# hb-featherwing_v2.net
KiCad netlist of a schematic drawn in EAGLE
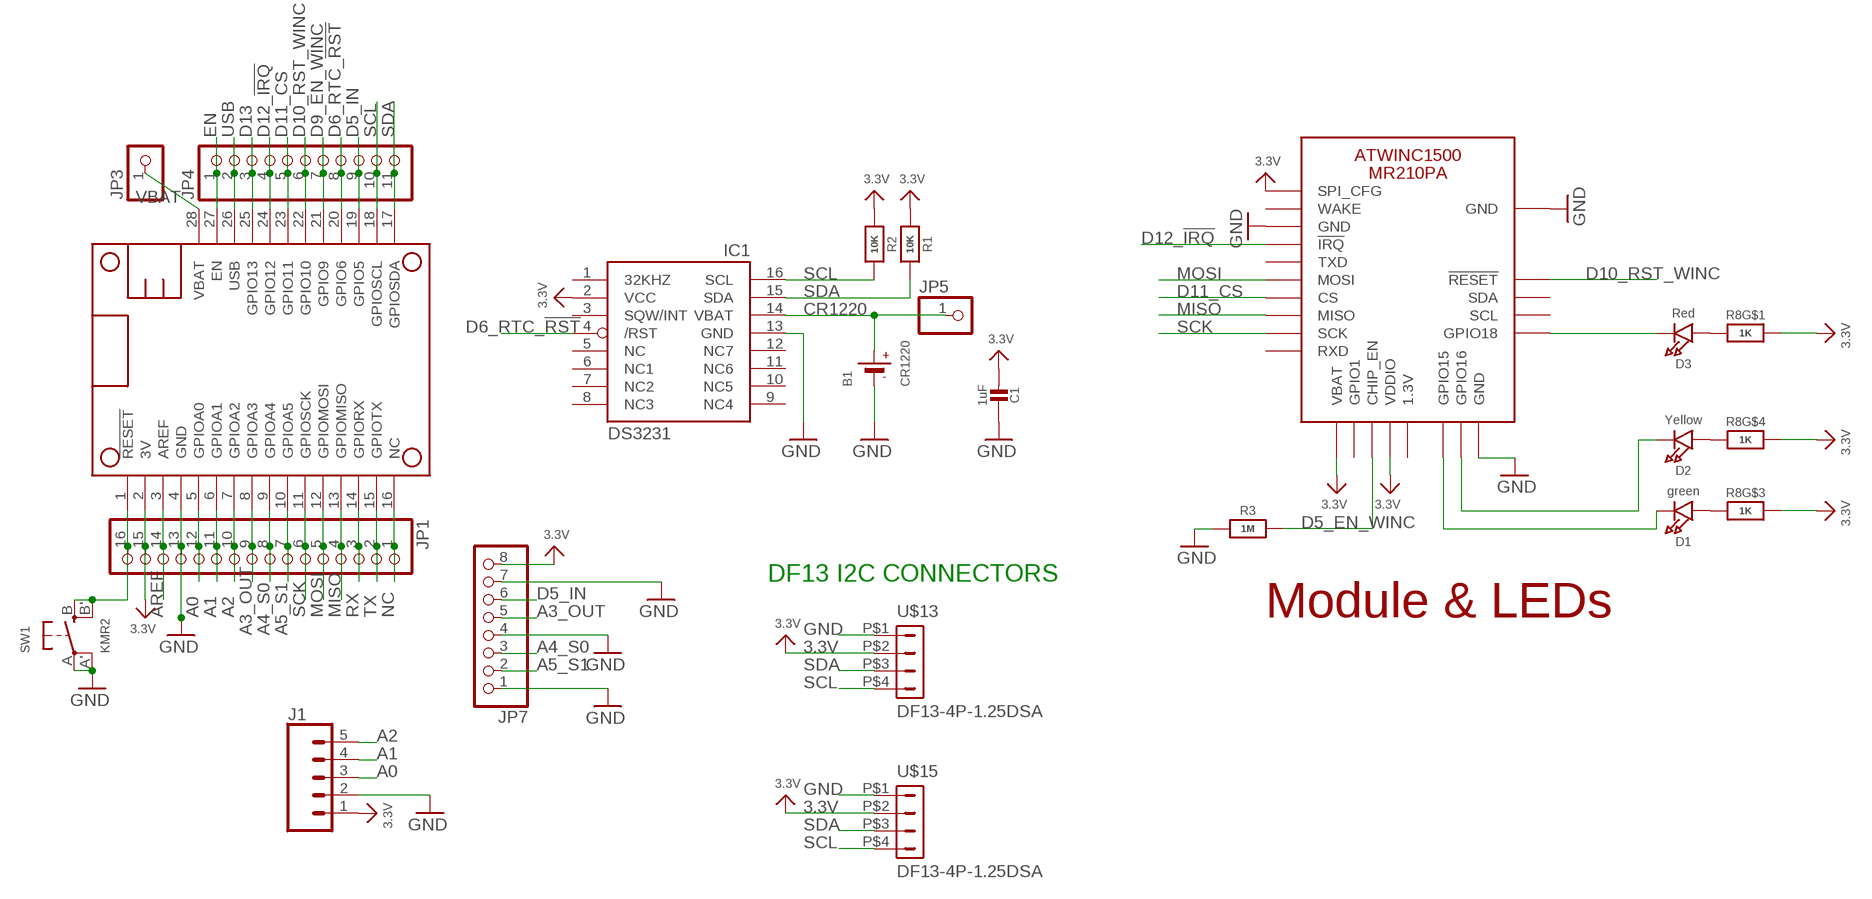
[diagram p0: schematic, sheet 1]

(export (version "E")
  (design (tool "Eeschema 10.0.6"))
  (components
    (comp (ref "B1")
      (value "CR1220")
      (footprint "eagle-import:CR1220-2")
      (libsource (lib "eagle-import") (part "BATTERYCR1220_2"))
    )
    (comp (ref "C1")
      (value "1uF")
      (footprint "eagle-import:0805-NO")
      (libsource (lib "eagle-import") (part "CAP_CERAMIC0805-NOOUTLINE"))
    )
    (comp (ref "D1")
      (value "green")
      (footprint "eagle-import:CHIPLED_0805_NOOUTLINE")
      (libsource (lib "eagle-import") (part "LED0805_NOOUTLINE"))
    )
    (comp (ref "D2")
      (value "Yellow")
      (footprint "eagle-import:CHIPLED_0805_NOOUTLINE")
      (libsource (lib "eagle-import") (part "LED0805_NOOUTLINE"))
    )
    (comp (ref "D3")
      (value "Red")
      (footprint "eagle-import:CHIPLED_0805_NOOUTLINE")
      (libsource (lib "eagle-import") (part "LED0805_NOOUTLINE"))
    )
    (comp (ref "IC1")
      (value "DS3231/SO")
      (footprint "eagle-import:SO16W")
      (libsource (lib "eagle-import") (part "DS3231/SO"))
    )
    (comp (ref "J1")
      (value "CONN_05")
      (footprint "eagle-import:1X05")
      (libsource (lib "eagle-import") (part "CONN_05"))
    )
    (comp (ref "JP1")
      (value "HEADER-1X16ROUND")
      (footprint "eagle-import:1X16_ROUND")
      (libsource (lib "eagle-import") (part "HEADER-1X16ROUND"))
    )
    (comp (ref "JP3")
      (value "HEADER-1X1ROUND")
      (footprint "eagle-import:1X01_ROUND")
      (libsource (lib "eagle-import") (part "HEADER-1X1ROUND"))
    )
    (comp (ref "JP4")
      (value "HEADER-1X11")
      (footprint "eagle-import:1X11_ROUND")
      (libsource (lib "eagle-import") (part "HEADER-1X11"))
    )
    (comp (ref "JP5")
      (value "HEADER-1X1ROUND")
      (footprint "eagle-import:1X01_ROUND")
      (libsource (lib "eagle-import") (part "HEADER-1X1ROUND"))
    )
    (comp (ref "JP7")
      (value "PINHD-1X8BIG")
      (footprint "eagle-import:1X08-BIG")
      (libsource (lib "eagle-import") (part "PINHD-1X8BIG"))
    )
    (comp (ref "MS1")
      (value "MICROSHIELD_NODIM")
      (footprint "eagle-import:MICROSHIELD_DIM")
      (libsource (lib "eagle-import") (part "MICROSHIELD_NODIM"))
    )
    (comp (ref "R1")
      (value "10K")
      (footprint "eagle-import:0805-NO")
      (libsource (lib "eagle-import") (part "RESISTOR0805_NOOUTLINE"))
    )
    (comp (ref "R2")
      (value "10K")
      (footprint "eagle-import:0805-NO")
      (libsource (lib "eagle-import") (part "RESISTOR0805_NOOUTLINE"))
    )
    (comp (ref "R3")
      (value "1M")
      (footprint "eagle-import:0805-NO")
      (libsource (lib "eagle-import") (part "RESISTOR0805_NOOUTLINE"))
    )
    (comp (ref "R8")
      (value "1K")
      (footprint "eagle-import:RESPACK_4X0603")
      (libsource (lib "eagle-import") (part "RESISTOR_4PACK"))
    )
    (comp (ref "SW1")
      (value "KMR2")
      (footprint "eagle-import:BTN_KMR2_4.6X2.8")
      (libsource (lib "eagle-import") (part "SWITCH_TACT_SMT4.6X2.8"))
    )
    (comp (ref "U$7")
      (value "ATWINC1500_MR210PB")
      (footprint "eagle-import:ATWINC1500_MR210PA")
      (libsource (lib "eagle-import") (part "ATWINC1500_MR210PA"))
    )
    (comp (ref "U$13")
      (value "DF13-4P-1.25DSA")
      (footprint "eagle-import:DF13-4P-1.25DSA")
      (libsource (lib "eagle-import") (part "DF13-4P-1.25DSA"))
    )
    (comp (ref "U$15")
      (value "DF13-4P-1.25DSA")
      (footprint "eagle-import:DF13-4P-1.25DSA")
      (libsource (lib "eagle-import") (part "DF13-4P-1.25DSA"))
    )
  )
  (nets
    (net (code "1") (name "/A0") (class "Default")
      (node (ref "J1") (pin "3") (pinfunction "3_3") (pintype "passive"))
      (node (ref "JP1") (pin "12") (pinfunction "12_12") (pintype "passive"))
      (node (ref "MS1") (pin "5") (pinfunction "GPIOA0_5") (pintype "bidirectional"))
    )
    (net (code "2") (name "/A1") (class "Default")
      (node (ref "J1") (pin "4") (pinfunction "4_4") (pintype "passive"))
      (node (ref "JP1") (pin "11") (pinfunction "11_11") (pintype "passive"))
      (node (ref "MS1") (pin "6") (pinfunction "GPIOA1_6") (pintype "bidirectional"))
    )
    (net (code "3") (name "/A2") (class "Default")
      (node (ref "J1") (pin "5") (pinfunction "5_5") (pintype "passive"))
      (node (ref "JP1") (pin "10") (pinfunction "10_10") (pintype "passive"))
      (node (ref "MS1") (pin "7") (pinfunction "GPIOA2_7") (pintype "bidirectional"))
    )
    (net (code "4") (name "/A3_OUT") (class "Default")
      (node (ref "JP1") (pin "9") (pinfunction "9_9") (pintype "passive"))
      (node (ref "JP7") (pin "5") (pinfunction "5_5") (pintype "passive"))
      (node (ref "MS1") (pin "8") (pinfunction "GPIOA3_8") (pintype "bidirectional"))
    )
    (net (code "5") (name "/A4_S0") (class "Default")
      (node (ref "JP1") (pin "8") (pinfunction "8_8") (pintype "passive"))
      (node (ref "JP7") (pin "3") (pinfunction "3_3") (pintype "passive"))
      (node (ref "MS1") (pin "9") (pinfunction "GPIOA4_9") (pintype "bidirectional"))
    )
    (net (code "6") (name "/A5_S1") (class "Default")
      (node (ref "JP1") (pin "7") (pinfunction "7_7") (pintype "passive"))
      (node (ref "JP7") (pin "2") (pinfunction "2_2") (pintype "passive"))
      (node (ref "MS1") (pin "10") (pinfunction "GPIOA5_10") (pintype "bidirectional"))
    )
    (net (code "7") (name "/AREF") (class "Default")
      (node (ref "JP1") (pin "14") (pinfunction "14_14") (pintype "passive"))
      (node (ref "MS1") (pin "3") (pinfunction "AREF_3") (pintype "passive"))
    )
    (net (code "8") (name "/CR1220") (class "Default")
      (node (ref "B1") (pin "+") (pinfunction "+_+") (pintype "passive"))
      (node (ref "IC1") (pin "14") (pinfunction "VBAT_14") (pintype "power_in"))
      (node (ref "JP5") (pin "1") (pinfunction "1_1") (pintype "passive"))
    )
    (net (code "9") (name "/D5_EN_WINC") (class "Default")
      (node (ref "R3") (pin "2") (pinfunction "2_2") (pintype "passive"))
      (node (ref "U$7") (pin "J22") (pinfunction "CHIP_EN_J22") (pintype "input"))
    )
    (net (code "10") (name "/D5_IN") (class "Default")
      (node (ref "JP4") (pin "9") (pinfunction "9_9") (pintype "passive"))
      (node (ref "JP7") (pin "6") (pinfunction "6_6") (pintype "passive"))
      (node (ref "MS1") (pin "19") (pinfunction "GPIO5_19") (pintype "bidirectional"))
    )
    (net (code "11") (name "/D6_RTC_~{RST}") (class "Default")
      (node (ref "IC1") (pin "4") (pinfunction "/RST_4") (pintype "passive"))
      (node (ref "JP4") (pin "8") (pinfunction "8_8") (pintype "passive"))
      (node (ref "MS1") (pin "20") (pinfunction "GPIO6_20") (pintype "bidirectional"))
    )
    (net (code "12") (name "/D9_EN_WINC") (class "Default")
      (node (ref "JP4") (pin "7") (pinfunction "7_7") (pintype "passive"))
      (node (ref "MS1") (pin "21") (pinfunction "GPIO9_21") (pintype "bidirectional"))
    )
    (net (code "13") (name "/D10_RST_WINC") (class "Default")
      (node (ref "JP4") (pin "6") (pinfunction "6_6") (pintype "passive"))
      (node (ref "MS1") (pin "22") (pinfunction "GPIO10_22") (pintype "bidirectional"))
      (node (ref "U$7") (pin "J4") (pinfunction "~{RESET}_J4") (pintype "input"))
    )
    (net (code "14") (name "/D11_CS") (class "Default")
      (node (ref "JP4") (pin "5") (pinfunction "5_5") (pintype "passive"))
      (node (ref "MS1") (pin "23") (pinfunction "GPIO11_23") (pintype "bidirectional"))
      (node (ref "U$7") (pin "J16") (pinfunction "CS_J16") (pintype "input"))
    )
    (net (code "15") (name "/D12_~{IRQ}") (class "Default")
      (node (ref "JP4") (pin "4") (pinfunction "4_4") (pintype "passive"))
      (node (ref "MS1") (pin "24") (pinfunction "GPIO12_24") (pintype "bidirectional"))
      (node (ref "U$7") (pin "J13") (pinfunction "~{IRQ}_J13") (pintype "output"))
    )
    (net (code "16") (name "/D13") (class "Default")
      (node (ref "JP4") (pin "3") (pinfunction "3_3") (pintype "passive"))
      (node (ref "MS1") (pin "25") (pinfunction "GPIO13_25") (pintype "bidirectional"))
    )
    (net (code "17") (name "/EN") (class "Default")
      (node (ref "JP4") (pin "1") (pinfunction "1_1") (pintype "passive"))
      (node (ref "MS1") (pin "27") (pinfunction "EN_27") (pintype "passive"))
    )
    (net (code "18") (name "/MISO") (class "Default")
      (node (ref "JP1") (pin "4") (pinfunction "4_4") (pintype "passive"))
      (node (ref "MS1") (pin "13") (pinfunction "GPIOMISO_13") (pintype "bidirectional"))
      (node (ref "U$7") (pin "J17") (pinfunction "MISO_J17") (pintype "output"))
    )
    (net (code "19") (name "/MOSI") (class "Default")
      (node (ref "JP1") (pin "5") (pinfunction "5_5") (pintype "passive"))
      (node (ref "MS1") (pin "12") (pinfunction "GPIOMOSI_12") (pintype "bidirectional"))
      (node (ref "U$7") (pin "J15") (pinfunction "MOSI_J15") (pintype "input"))
    )
    (net (code "20") (name "/NC") (class "Default")
      (node (ref "JP1") (pin "1") (pinfunction "1_1") (pintype "passive"))
      (node (ref "MS1") (pin "16") (pinfunction "NC_16") (pintype "passive"))
    )
    (net (code "21") (name "/RX") (class "Default")
      (node (ref "JP1") (pin "3") (pinfunction "3_3") (pintype "passive"))
      (node (ref "MS1") (pin "14") (pinfunction "GPIORX_14") (pintype "bidirectional"))
    )
    (net (code "22") (name "/SCK") (class "Default")
      (node (ref "JP1") (pin "6") (pinfunction "6_6") (pintype "passive"))
      (node (ref "MS1") (pin "11") (pinfunction "GPIOSCK_11") (pintype "bidirectional"))
      (node (ref "U$7") (pin "J18") (pinfunction "SCK_J18") (pintype "input"))
    )
    (net (code "23") (name "/SCL") (class "Default")
      (node (ref "IC1") (pin "16") (pinfunction "SCL_16") (pintype "bidirectional"))
      (node (ref "JP4") (pin "10") (pinfunction "10_10") (pintype "passive"))
      (node (ref "MS1") (pin "18") (pinfunction "GPIOSCL_18") (pintype "bidirectional"))
      (node (ref "R2") (pin "2") (pinfunction "2_2") (pintype "passive"))
      (node (ref "U$13") (pin "P$4") (pinfunction "4_P$4") (pintype "passive"))
      (node (ref "U$15") (pin "P$4") (pinfunction "4_P$4") (pintype "passive"))
    )
    (net (code "24") (name "/SDA") (class "Default")
      (node (ref "IC1") (pin "15") (pinfunction "SDA_15") (pintype "bidirectional"))
      (node (ref "JP4") (pin "11") (pinfunction "11_11") (pintype "passive"))
      (node (ref "MS1") (pin "17") (pinfunction "GPIOSDA_17") (pintype "bidirectional"))
      (node (ref "R1") (pin "2") (pinfunction "2_2") (pintype "passive"))
      (node (ref "U$13") (pin "P$3") (pinfunction "3_P$3") (pintype "passive"))
      (node (ref "U$15") (pin "P$3") (pinfunction "3_P$3") (pintype "passive"))
    )
    (net (code "25") (name "/TX") (class "Default")
      (node (ref "JP1") (pin "2") (pinfunction "2_2") (pintype "passive"))
      (node (ref "MS1") (pin "15") (pinfunction "GPIOTX_15") (pintype "bidirectional"))
    )
    (net (code "26") (name "/USB") (class "Default")
      (node (ref "JP4") (pin "2") (pinfunction "2_2") (pintype "passive"))
      (node (ref "MS1") (pin "26") (pinfunction "USB_26") (pintype "power_in"))
    )
    (net (code "27") (name "/VBAT") (class "Default")
      (node (ref "JP3") (pin "1") (pinfunction "1_1") (pintype "passive"))
      (node (ref "MS1") (pin "28") (pinfunction "VBAT_28") (pintype "power_in"))
    )
    (net (code "28") (name "3.3V") (class "Default")
      (node (ref "C1") (pin "2") (pinfunction "2_2") (pintype "passive"))
      (node (ref "IC1") (pin "2") (pinfunction "VCC_2") (pintype "power_in"))
      (node (ref "J1") (pin "1") (pinfunction "1_1") (pintype "passive"))
      (node (ref "JP1") (pin "15") (pinfunction "15_15") (pintype "passive"))
      (node (ref "JP7") (pin "8") (pinfunction "8_8") (pintype "passive"))
      (node (ref "MS1") (pin "2") (pinfunction "3V_2") (pintype "power_in"))
      (node (ref "R1") (pin "1") (pinfunction "1_1") (pintype "passive"))
      (node (ref "R2") (pin "1") (pinfunction "1_1") (pintype "passive"))
      (node (ref "R8") (pin "5") (pinfunction "2_5") (pintype "passive"))
      (node (ref "R8") (pin "6") (pinfunction "2_6") (pintype "passive"))
      (node (ref "R8") (pin "8") (pinfunction "2_8") (pintype "passive"))
      (node (ref "U$13") (pin "P$2") (pinfunction "2_P$2") (pintype "passive"))
      (node (ref "U$15") (pin "P$2") (pinfunction "2_P$2") (pintype "passive"))
      (node (ref "U$7") (pin "J10") (pinfunction "SPI_CFG_J10") (pintype "input"))
      (node (ref "U$7") (pin "J20") (pinfunction "VBAT_J20") (pintype "power_in"))
      (node (ref "U$7") (pin "J23") (pinfunction "VDDIO_J23") (pintype "power_in"))
    )
    (net (code "29") (name "GND") (class "Default")
      (node (ref "B1") (pin "-") (pinfunction "-_-") (pintype "passive"))
      (node (ref "C1") (pin "1") (pinfunction "1_1") (pintype "passive"))
      (node (ref "IC1") (pin "13") (pinfunction "GND_13") (pintype "power_in"))
      (node (ref "J1") (pin "2") (pinfunction "2_2") (pintype "passive"))
      (node (ref "JP1") (pin "13") (pinfunction "13_13") (pintype "passive"))
      (node (ref "JP7") (pin "1") (pinfunction "1_1") (pintype "passive"))
      (node (ref "JP7") (pin "4") (pinfunction "4_4") (pintype "passive"))
      (node (ref "JP7") (pin "7") (pinfunction "7_7") (pintype "passive"))
      (node (ref "MS1") (pin "4") (pinfunction "GND_4") (pintype "power_in"))
      (node (ref "R3") (pin "1") (pinfunction "1_1") (pintype "passive"))
      (node (ref "SW1") (pin "A") (pinfunction "P_A") (pintype "passive"))
      (node (ref "SW1") (pin "A'") (pinfunction "P1_A'") (pintype "passive"))
      (node (ref "U$13") (pin "P$1") (pinfunction "1_P$1") (pintype "passive"))
      (node (ref "U$15") (pin "P$1") (pinfunction "1_P$1") (pintype "passive"))
      (node (ref "U$7") (pin "J12") (pinfunction "GND_J12") (pintype "power_in"))
      (node (ref "U$7") (pin "J28") (pinfunction "GND_J28") (pintype "power_in"))
      (node (ref "U$7") (pin "J9") (pinfunction "GND_J9") (pintype "bidirectional"))
      (node (ref "U$7") (pin "MTGND") (pinfunction "GND_MTGND") (pintype "power_in"))
    )
    (net (code "30") (name "Net-(D3-PadA)") (class "Default")
      (node (ref "D3") (pin "A") (pinfunction "A_A") (pintype "passive"))
      (node (ref "R8") (pin "1") (pinfunction "1_1") (pintype "passive"))
    )
    (net (code "31") (name "Net-(MS1-~{RESET})") (class "Default")
      (node (ref "JP1") (pin "16") (pinfunction "16_16") (pintype "passive"))
      (node (ref "MS1") (pin "1") (pinfunction "~{RESET}_1") (pintype "input"))
      (node (ref "SW1") (pin "B") (pinfunction "S_B") (pintype "passive"))
      (node (ref "SW1") (pin "B'") (pinfunction "S1_B'") (pintype "passive"))
    )
    (net (code "32") (name "Net-(R8C-1)") (class "Default")
      (node (ref "D1") (pin "A") (pinfunction "A_A") (pintype "passive"))
      (node (ref "R8") (pin "3") (pinfunction "1_3") (pintype "passive"))
    )
    (net (code "33") (name "Net-(R8D-1)") (class "Default")
      (node (ref "D2") (pin "A") (pinfunction "A_A") (pintype "passive"))
      (node (ref "R8") (pin "4") (pinfunction "1_4") (pintype "passive"))
    )
    (net (code "34") (name "Net-(U$7-GPIO15)") (class "Default")
      (node (ref "D1") (pin "C") (pinfunction "C_C") (pintype "passive"))
      (node (ref "U$7") (pin "J26") (pinfunction "GPIO15_J26") (pintype "bidirectional"))
    )
    (net (code "35") (name "Net-(U$7-GPIO16)") (class "Default")
      (node (ref "D2") (pin "C") (pinfunction "C_C") (pintype "passive"))
      (node (ref "U$7") (pin "J27") (pinfunction "GPIO16_J27") (pintype "bidirectional"))
    )
    (net (code "36") (name "Net-(U$7-GPIO18)") (class "Default")
      (node (ref "D3") (pin "C") (pinfunction "C_C") (pintype "passive"))
      (node (ref "U$7") (pin "J1") (pinfunction "GPIO18_J1") (pintype "bidirectional"))
    )
    (net (code "37") (name "unconnected-(IC1-32KHZ-Pad1)") (class "Default")
      (node (ref "IC1") (pin "1") (pinfunction "32KHZ_1") (pintype "output"))
    )
    (net (code "38") (name "unconnected-(IC1-NC-Pad5)") (class "Default")
      (node (ref "IC1") (pin "5") (pinfunction "NC_5") (pintype "no_connect"))
    )
    (net (code "39") (name "unconnected-(IC1-NC1-Pad6)") (class "Default")
      (node (ref "IC1") (pin "6") (pinfunction "NC1_6") (pintype "no_connect"))
    )
    (net (code "40") (name "unconnected-(IC1-NC2-Pad7)") (class "Default")
      (node (ref "IC1") (pin "7") (pinfunction "NC2_7") (pintype "no_connect"))
    )
    (net (code "41") (name "unconnected-(IC1-NC3-Pad8)") (class "Default")
      (node (ref "IC1") (pin "8") (pinfunction "NC3_8") (pintype "no_connect"))
    )
    (net (code "42") (name "unconnected-(IC1-NC4-Pad9)") (class "Default")
      (node (ref "IC1") (pin "9") (pinfunction "NC4_9") (pintype "no_connect"))
    )
    (net (code "43") (name "unconnected-(IC1-NC5-Pad10)") (class "Default")
      (node (ref "IC1") (pin "10") (pinfunction "NC5_10") (pintype "no_connect"))
    )
    (net (code "44") (name "unconnected-(IC1-NC6-Pad11)") (class "Default")
      (node (ref "IC1") (pin "11") (pinfunction "NC6_11") (pintype "no_connect"))
    )
    (net (code "45") (name "unconnected-(IC1-NC7-Pad12)") (class "Default")
      (node (ref "IC1") (pin "12") (pinfunction "NC7_12") (pintype "no_connect"))
    )
    (net (code "46") (name "unconnected-(IC1-SQW{slash}INT-Pad3)") (class "Default")
      (node (ref "IC1") (pin "3") (pinfunction "SQW/INT_3") (pintype "output"))
    )
    (net (code "47") (name "unconnected-(U$7-1.3V-PadJ24)") (class "Default")
      (node (ref "U$7") (pin "J24") (pinfunction "1.3V_J24") (pintype "passive"))
    )
    (net (code "48") (name "unconnected-(U$7-GPIO1-PadJ21)") (class "Default")
      (node (ref "U$7") (pin "J21") (pinfunction "GPIO1_J21") (pintype "bidirectional"))
    )
    (net (code "49") (name "unconnected-(U$7-RXD-PadJ19)") (class "Default")
      (node (ref "U$7") (pin "J19") (pinfunction "RXD_J19") (pintype "input"))
    )
    (net (code "50") (name "unconnected-(U$7-SCL-PadJ2)") (class "Default")
      (node (ref "U$7") (pin "J2") (pinfunction "SCL_J2") (pintype "bidirectional"))
    )
    (net (code "51") (name "unconnected-(U$7-SDA-PadJ3)") (class "Default")
      (node (ref "U$7") (pin "J3") (pinfunction "SDA_J3") (pintype "bidirectional"))
    )
    (net (code "52") (name "unconnected-(U$7-TXD-PadJ14)") (class "Default")
      (node (ref "U$7") (pin "J14") (pinfunction "TXD_J14") (pintype "output"))
    )
    (net (code "53") (name "unconnected-(U$7-WAKE-PadJ11)") (class "Default")
      (node (ref "U$7") (pin "J11") (pinfunction "WAKE_J11") (pintype "input"))
    )
  )
)
